# weather.net
KiCad netlist of a schematic drawn in EasyEDA Pro
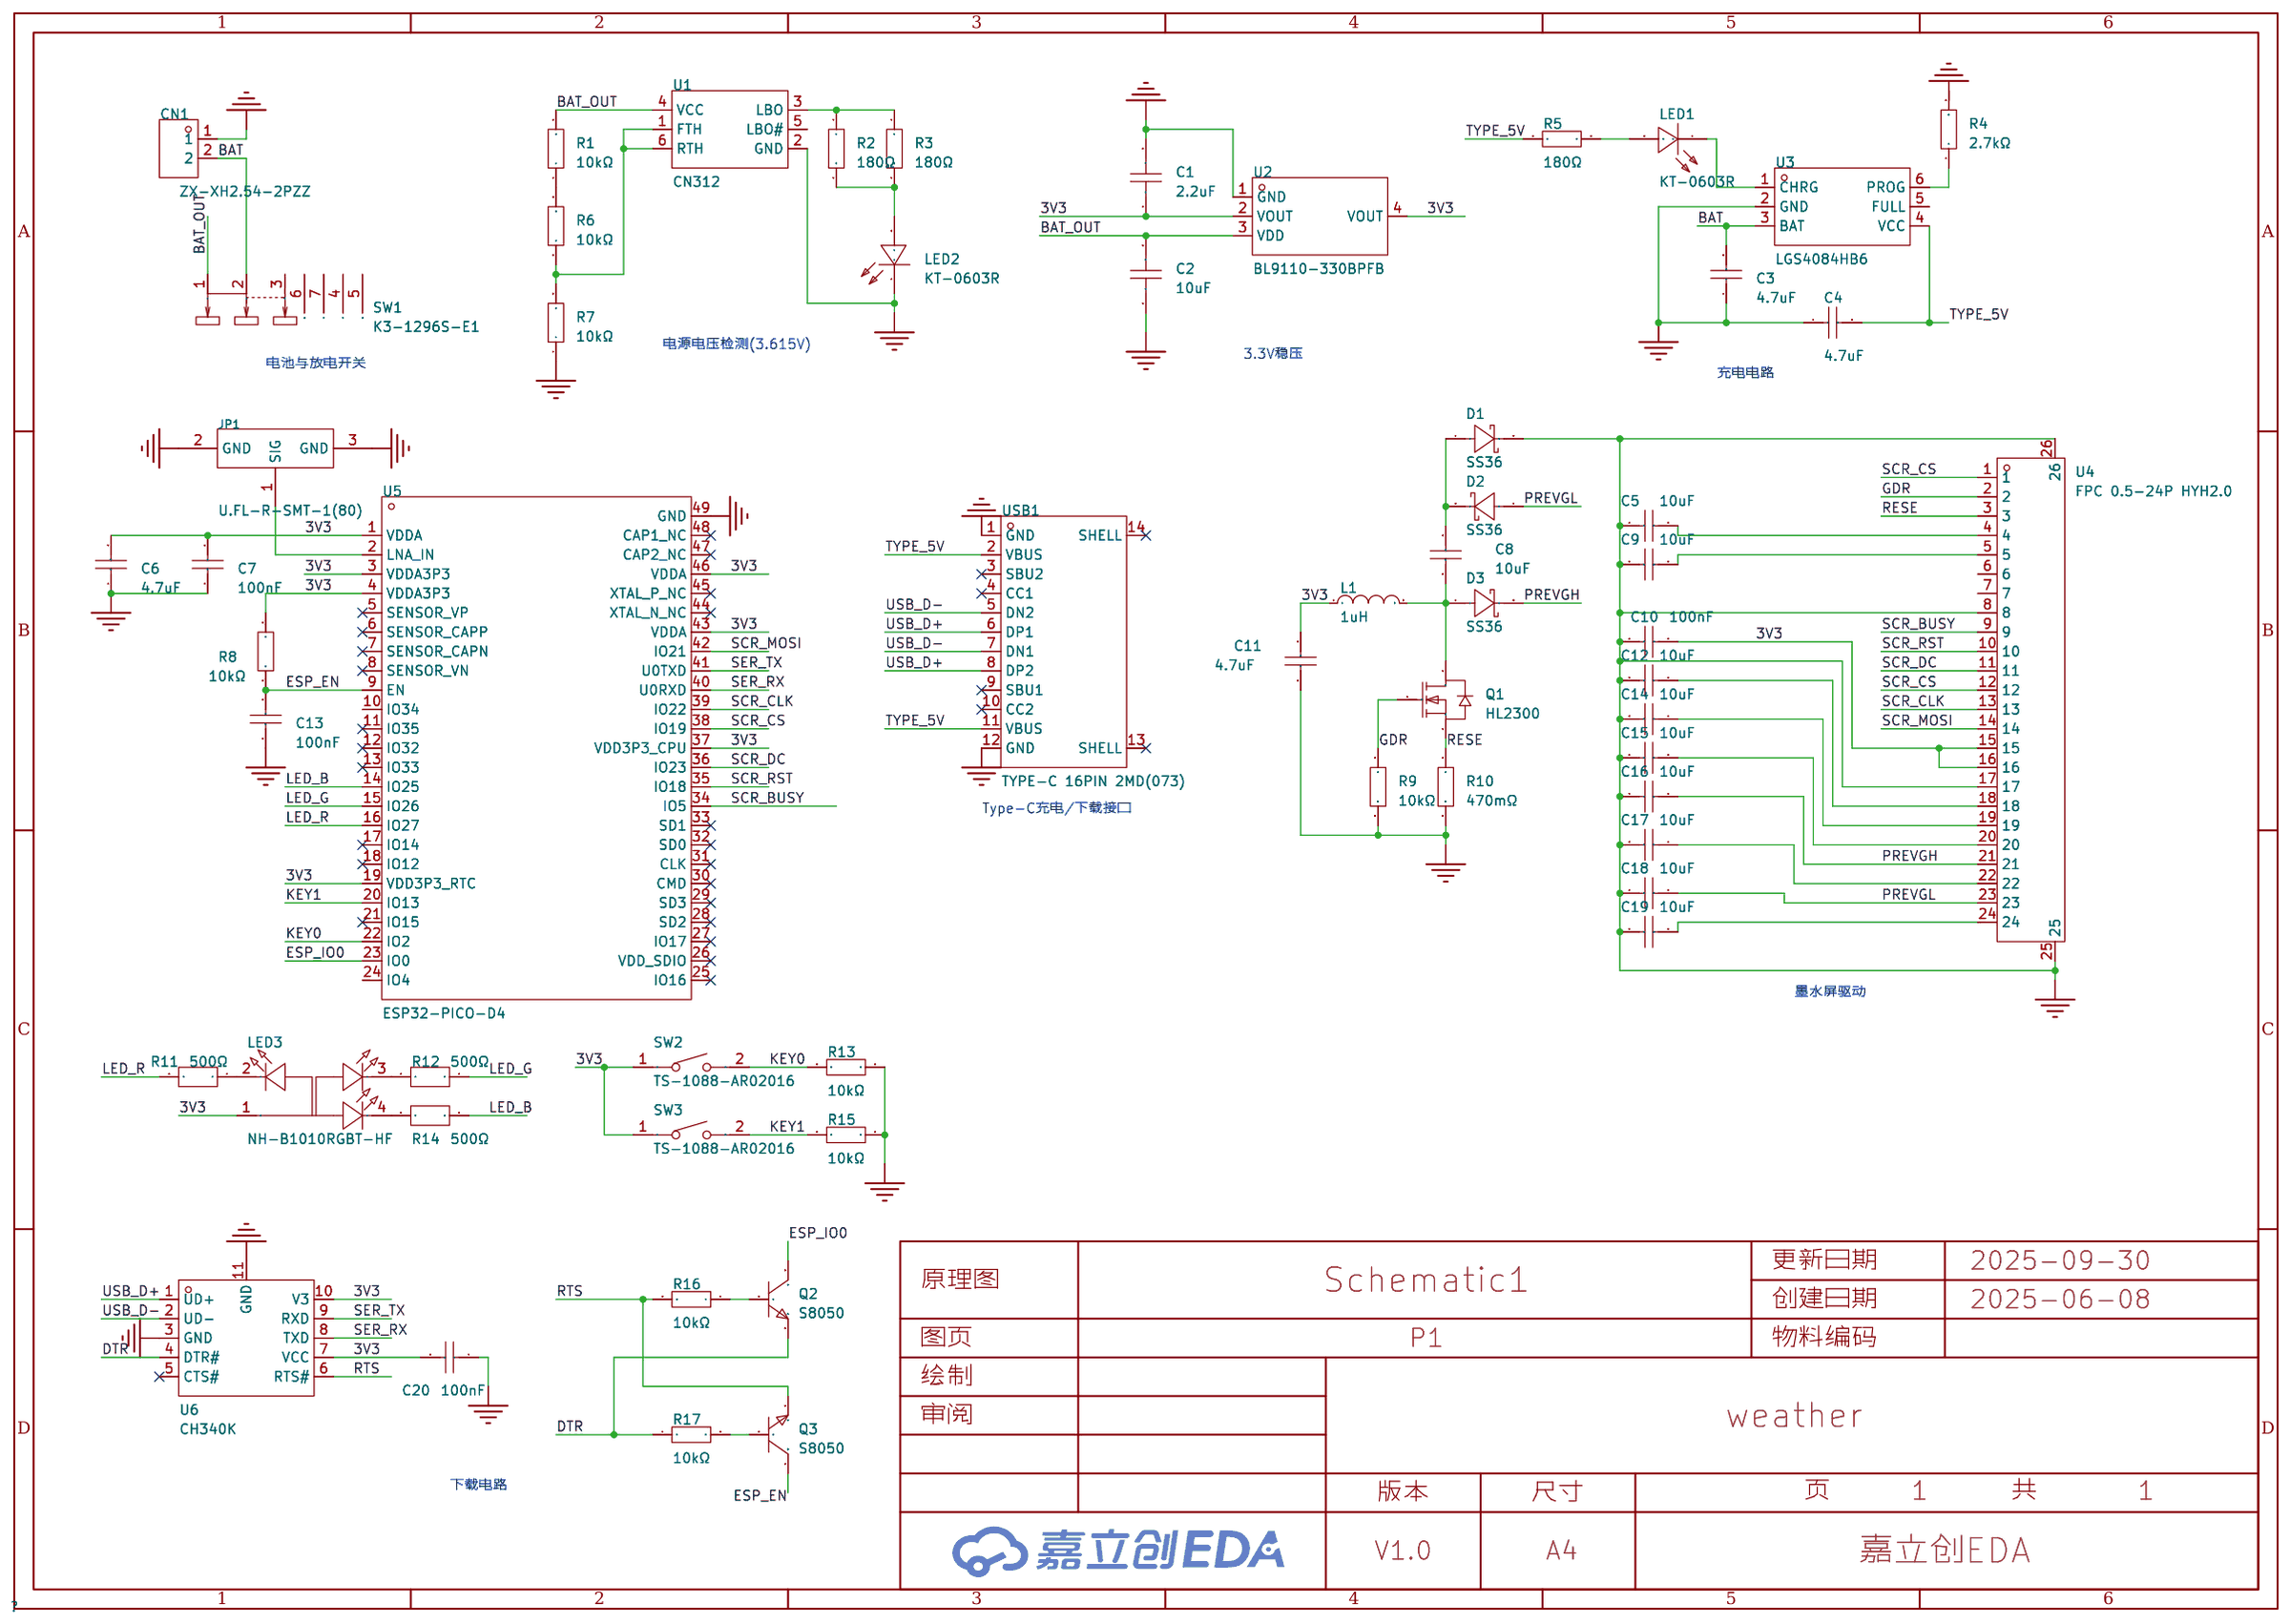
[diagram p0: schematic sheet]

(export (version "E")
  (design (tool "Eeschema 10.0.6"))
  (components
    (comp (ref "C1")
      (value "2.2uF")
      (footprint "easyedapro:C0402")
      (description "容值:2.2uF;精度:±10%;额定电压:16V;材质(温度系数):X5R;")
      (fields
        (field (name "Manufacturer Part") "HGC0402R5225K160NTEJ")
        (field (name "Manufacturer") "Chinocera(华瓷)")
      )
      (libsource (lib "easyedapro") (part "HGC0402R5225K160NTEJ"))
    )
    (comp (ref "C2")
      (value "10uF")
      (footprint "easyedapro:C0402")
      (description "容值:10uF;精度:±20%;额定电压:10V;材质(温度系数):X5R;")
      (fields
        (field (name "Manufacturer Part") "CGA0402X5R106M100GT")
        (field (name "Manufacturer") "HRE(芯声)")
      )
      (libsource (lib "easyedapro") (part "CGA0402X5R106M100GT"))
    )
    (comp (ref "C3")
      (value "4.7uF")
      (footprint "easyedapro:C0402")
      (description "容值:10uF;精度:±20%;额定电压:6.3V;材质(温度系数):X5R;")
      (fields
        (field (name "Manufacturer Part") "CL05A475MP5NRNC")
        (field (name "Manufacturer") "SAMSUNG(三星)")
      )
      (libsource (lib "easyedapro") (part "CL05A106MQ5NUNC"))
    )
    (comp (ref "C4")
      (value "4.7uF")
      (footprint "easyedapro:C0402")
      (description "容值:10uF;精度:±20%;额定电压:6.3V;材质(温度系数):X5R;")
      (fields
        (field (name "Manufacturer Part") "CL05A475MP5NRNC")
        (field (name "Manufacturer") "SAMSUNG(三星)")
      )
      (libsource (lib "easyedapro") (part "CL05A106MQ5NUNC"))
    )
    (comp (ref "C5")
      (value "10uF")
      (footprint "easyedapro:C0402")
      (description "容值:10uF;精度:±20%;额定电压:6.3V;材质(温度系数):X5R;")
      (fields
        (field (name "Manufacturer Part") "CL05A106MQ5NUNC")
        (field (name "Manufacturer") "SAMSUNG(三星)")
      )
      (libsource (lib "easyedapro") (part "CL05A106MQ5NUNC"))
    )
    (comp (ref "C6")
      (value "4.7uF")
      (footprint "easyedapro:C0402")
      (description "容值:10uF;精度:±20%;额定电压:6.3V;材质(温度系数):X5R;")
      (fields
        (field (name "Manufacturer Part") "CL05A475MP5NRNC")
        (field (name "Manufacturer") "SAMSUNG(三星)")
      )
      (libsource (lib "easyedapro") (part "CL05A106MQ5NUNC"))
    )
    (comp (ref "C7")
      (value "100nF")
      (footprint "easyedapro:C0402")
      (description "容值:100nF;精度:±10%;额定电压:16V;材质(温度系数):X7R;")
      (fields
        (field (name "Manufacturer Part") "CL05B104KO5NNNC")
        (field (name "Manufacturer") "SAMSUNG(三星)")
      )
      (libsource (lib "easyedapro") (part "CL05B104KO5NNNC"))
    )
    (comp (ref "C8")
      (value "10uF")
      (footprint "easyedapro:C0402")
      (description "容值:100nF;精度:±10%;额定电压:16V;温度系数:X7R;")
      (fields
        (field (name "Manufacturer Part") "CL05A106MQ5NUNC")
        (field (name "Manufacturer") "SAMSUNG(三星)")
      )
      (libsource (lib "easyedapro") (part "CL05A106MQ5NUNC"))
    )
    (comp (ref "C9")
      (value "10uF")
      (footprint "easyedapro:C0402")
      (description "容值:10uF;精度:±20%;额定电压:6.3V;材质(温度系数):X5R;")
      (fields
        (field (name "Manufacturer Part") "CL05A106MQ5NUNC")
        (field (name "Manufacturer") "SAMSUNG(三星)")
      )
      (libsource (lib "easyedapro") (part "CL05A106MQ5NUNC"))
    )
    (comp (ref "C10")
      (value "100nF")
      (footprint "easyedapro:C0402")
      (description "容值:100nF;精度:±10%;额定电压:16V;材质(温度系数):X7R;")
      (fields
        (field (name "Manufacturer Part") "CL05B104KO5NNNC")
        (field (name "Manufacturer") "SAMSUNG(三星)")
      )
      (libsource (lib "easyedapro") (part "CL05B104KO5NNNC"))
    )
    (comp (ref "C11")
      (value "4.7uF")
      (footprint "easyedapro:C0402")
      (description "容值:10uF;精度:±20%;额定电压:6.3V;材质(温度系数):X5R;")
      (fields
        (field (name "Manufacturer Part") "CL05A475MP5NRNC")
        (field (name "Manufacturer") "SAMSUNG(三星)")
      )
      (libsource (lib "easyedapro") (part "CL05A106MQ5NUNC"))
    )
    (comp (ref "C12")
      (value "10uF")
      (footprint "easyedapro:C0402")
      (description "容值:10uF;精度:±20%;额定电压:6.3V;材质(温度系数):X5R;")
      (fields
        (field (name "Manufacturer Part") "CL05A106MQ5NUNC")
        (field (name "Manufacturer") "SAMSUNG(三星)")
      )
      (libsource (lib "easyedapro") (part "CL05A106MQ5NUNC"))
    )
    (comp (ref "C13")
      (value "100nF")
      (footprint "easyedapro:C0402")
      (description "容值:100nF;精度:±10%;额定电压:16V;材质(温度系数):X7R;")
      (fields
        (field (name "Manufacturer Part") "CL05B104KO5NNNC")
        (field (name "Manufacturer") "SAMSUNG(三星)")
      )
      (libsource (lib "easyedapro") (part "CL05B104KO5NNNC"))
    )
    (comp (ref "C14")
      (value "10uF")
      (footprint "easyedapro:C0402")
      (description "容值:10uF;精度:±20%;额定电压:6.3V;材质(温度系数):X5R;")
      (fields
        (field (name "Manufacturer Part") "CL05A106MQ5NUNC")
        (field (name "Manufacturer") "SAMSUNG(三星)")
      )
      (libsource (lib "easyedapro") (part "CL05A106MQ5NUNC"))
    )
    (comp (ref "C15")
      (value "10uF")
      (footprint "easyedapro:C0402")
      (description "容值:10uF;精度:±20%;额定电压:6.3V;材质(温度系数):X5R;")
      (fields
        (field (name "Manufacturer Part") "CL05A106MQ5NUNC")
        (field (name "Manufacturer") "SAMSUNG(三星)")
      )
      (libsource (lib "easyedapro") (part "CL05A106MQ5NUNC"))
    )
    (comp (ref "C16")
      (value "10uF")
      (footprint "easyedapro:C0402")
      (description "容值:10uF;精度:±20%;额定电压:6.3V;材质(温度系数):X5R;")
      (fields
        (field (name "Manufacturer Part") "CL05A106MQ5NUNC")
        (field (name "Manufacturer") "SAMSUNG(三星)")
      )
      (libsource (lib "easyedapro") (part "CL05A106MQ5NUNC"))
    )
    (comp (ref "C17")
      (value "10uF")
      (footprint "easyedapro:C0402")
      (description "容值:10uF;精度:±20%;额定电压:6.3V;材质(温度系数):X5R;")
      (fields
        (field (name "Manufacturer Part") "CL05A106MQ5NUNC")
        (field (name "Manufacturer") "SAMSUNG(三星)")
      )
      (libsource (lib "easyedapro") (part "CL05A106MQ5NUNC"))
    )
    (comp (ref "C18")
      (value "10uF")
      (footprint "easyedapro:C0402")
      (description "容值:10uF;精度:±20%;额定电压:6.3V;材质(温度系数):X5R;")
      (fields
        (field (name "Manufacturer Part") "CL05A106MQ5NUNC")
        (field (name "Manufacturer") "SAMSUNG(三星)")
      )
      (libsource (lib "easyedapro") (part "CL05A106MQ5NUNC"))
    )
    (comp (ref "C19")
      (value "10uF")
      (footprint "easyedapro:C0402")
      (description "容值:10uF;精度:±20%;额定电压:6.3V;材质(温度系数):X5R;")
      (fields
        (field (name "Manufacturer Part") "CL05A106MQ5NUNC")
        (field (name "Manufacturer") "SAMSUNG(三星)")
      )
      (libsource (lib "easyedapro") (part "CL05A106MQ5NUNC"))
    )
    (comp (ref "C20")
      (value "100nF")
      (footprint "easyedapro:C0402")
      (description "容值:100nF;精度:±10%;额定电压:16V;材质(温度系数):X7R;")
      (fields
        (field (name "Manufacturer Part") "CL05B104KO5NNNC")
        (field (name "Manufacturer") "SAMSUNG(三星)")
      )
      (libsource (lib "easyedapro") (part "CL05B104KO5NNNC"))
    )
    (comp (ref "CN1")
      (value "ZX-XH2.54-2PZZ")
      (footprint "easyedapro:CONN-TH_2P-P2.50_HX25003-2A")
      (fields (field (name "Manufacturer") "Megastar(兆星)"))
      (libsource (lib "easyedapro") (part "ZX-XH2.54-2PZZ"))
    )
    (comp (ref "D1")
      (value "SS36")
      (footprint "easyedapro:SMA_L4.3-W2.6-LS5.0-FD")
      (description "二极管配置:独立式;正向压降(Vf):700mV@3.0A;直流反向耐压(Vr):60V;整流电流:3A;")
      (fields (field (name "Manufacturer") "R+O(宏嘉诚)"))
      (libsource (lib "easyedapro") (part "SS36_C7420367"))
    )
    (comp (ref "D2")
      (value "SS36")
      (footprint "easyedapro:SMA_L4.3-W2.6-LS5.0-FD")
      (description "二极管配置:独立式;正向压降(Vf):700mV@3.0A;直流反向耐压(Vr):60V;整流电流:3A;")
      (fields (field (name "Manufacturer") "R+O(宏嘉诚)"))
      (libsource (lib "easyedapro") (part "SS36_C7420367"))
    )
    (comp (ref "D3")
      (value "SS36")
      (footprint "easyedapro:SMA_L4.3-W2.6-LS5.0-FD")
      (description "二极管配置:独立式;正向压降(Vf):700mV@3.0A;直流反向耐压(Vr):60V;整流电流:3A;")
      (fields (field (name "Manufacturer") "R+O(宏嘉诚)"))
      (libsource (lib "easyedapro") (part "SS36_C7420367"))
    )
    (comp (ref "JP1")
      (value "U.FL-R-SMT-1(80)")
      (footprint "easyedapro:RF-SMD_FRF05002-JSS103M")
      (fields (field (name "Manufacturer") "HRS(广濑)"))
      (libsource (lib "easyedapro") (part "U.FL-R-SMT-1(80)"))
    )
    (comp (ref "L1")
      (value "1uH")
      (footprint "easyedapro:IND-SMD_L2.0-W1.6-B")
      (description "电感值:1uH;精度:±20%;额定电流:4.5A;饱和电流(Isat):4.6A;类型:一体成型电感;")
      (fields
        (field (name "Manufacturer Part") "FTC201610S1R0MBCA")
        (field (name "Manufacturer") "cjiang(长江微电)")
      )
      (libsource (lib "easyedapro") (part "FTC201610S1R0MBCA"))
    )
    (comp (ref "LED1")
      (value "KT-0603R")
      (footprint "easyedapro:LED0603-RD")
      (description "发光颜色:红色;功率:-;正向电流:-;主波长:-;二极管配置:-;透镜颜色:-;色温:-;发光角度:-;载带方式:-;工作温度:-40°C~+85°C;")
      (fields (field (name "Manufacturer") "KENTO"))
      (libsource (lib "easyedapro") (part "KT-0603R"))
    )
    (comp (ref "LED2")
      (value "KT-0603R")
      (footprint "easyedapro:LED0603-RD")
      (description "发光颜色:红色;功率:-;正向电流:-;主波长:-;二极管配置:-;透镜颜色:-;色温:-;发光角度:-;载带方式:-;工作温度:-40°C~+85°C;")
      (fields (field (name "Manufacturer") "KENTO"))
      (libsource (lib "easyedapro") (part "KT-0603R"))
    )
    (comp (ref "LED3")
      (value "NH-B1010RGBT-HF")
      (footprint "easyedapro:LED-ARRAY-SMD_4P-L1.0-W1.0-TR_NH-B1010RGBT")
      (description "户内RGB，全黑框架，对比度高，黑色哑光封装，无镜面反射")
      (fields (field (name "Manufacturer") "国星光电"))
      (libsource (lib "easyedapro") (part "NH-B1010RGBT-HF"))
    )
    (comp (ref "Q1")
      (value "HL2300")
      (footprint "easyedapro:SOT-23-3_L2.9-W1.3-P1.90-LS2.4-BR")
      (fields (field (name "Manufacturer") "R+O(宏嘉诚)"))
      (libsource (lib "easyedapro") (part "HL2300_C7420343"))
    )
    (comp (ref "Q2")
      (value "S8050")
      (footprint "easyedapro:SOT-23-3_L2.9-W1.6-P1.90-LS2.8-BR")
      (description "晶体管类型:NPN;集电极电流(Ic):500mA;集射极击穿电压(Vceo):25V;功率(Pd):300mW;")
      (fields (field (name "Manufacturer") "Hottech(合科泰)"))
      (libsource (lib "easyedapro") (part "S8050_C181158"))
    )
    (comp (ref "Q3")
      (value "S8050")
      (footprint "easyedapro:SOT-23-3_L2.9-W1.6-P1.90-LS2.8-BR")
      (description "晶体管类型:NPN;集电极电流(Ic):500mA;集射极击穿电压(Vceo):25V;功率(Pd):300mW;")
      (fields (field (name "Manufacturer") "Hottech(合科泰)"))
      (libsource (lib "easyedapro") (part "S8050_C181158"))
    )
    (comp (ref "R1")
      (value "10kΩ")
      (footprint "easyedapro:R0603")
      (description "电阻类型:厚膜电阻;阻值:10kΩ;精度:±1%;功率:100mW;最大工作电压:75V;温度系数:±100ppm/°C;")
      (fields
        (field (name "Manufacturer Part") "0402WGF1002TCE")
        (field (name "Manufacturer") "UNI-ROYAL(厚声)")
      )
      (libsource (lib "easyedapro") (part "0603WAF1002T5E"))
    )
    (comp (ref "R2")
      (value "180Ω")
      (fields
        (field (name "Manufacturer Part") "0402WGF1800TCE")
        (field (name "Manufacturer") "UNI-ROYAL(厚声)")
      )
      (libsource (lib "easyedapro") (part "0603WAF1800T5E"))
    )
    (comp (ref "R3")
      (value "180Ω")
      (fields
        (field (name "Manufacturer Part") "0402WGF1800TCE")
        (field (name "Manufacturer") "UNI-ROYAL(厚声)")
      )
      (libsource (lib "easyedapro") (part "0603WAF1800T5E"))
    )
    (comp (ref "R4")
      (value "2.7kΩ")
      (footprint "easyedapro:R0402")
      (description "电阻类型:厚膜电阻;阻值:2.7kΩ;精度:±1%;功率:62.5mW;最大工作电压:50V;温度系数:±100ppm/°C;")
      (fields
        (field (name "Manufacturer Part") "0402WGF2701TCE")
        (field (name "Manufacturer") "UNI-ROYAL(厚声)")
      )
      (libsource (lib "easyedapro") (part "0402WGF2701TCE"))
    )
    (comp (ref "R5")
      (value "180Ω")
      (fields
        (field (name "Manufacturer Part") "0402WGF1800TCE")
        (field (name "Manufacturer") "UNI-ROYAL(厚声)")
      )
      (libsource (lib "easyedapro") (part "0603WAF1800T5E"))
    )
    (comp (ref "R6")
      (value "10kΩ")
      (footprint "easyedapro:R0603")
      (description "电阻类型:厚膜电阻;阻值:10kΩ;精度:±1%;功率:100mW;最大工作电压:75V;温度系数:±100ppm/°C;")
      (fields
        (field (name "Manufacturer Part") "0402WGF1002TCE")
        (field (name "Manufacturer") "UNI-ROYAL(厚声)")
      )
      (libsource (lib "easyedapro") (part "0603WAF1002T5E"))
    )
    (comp (ref "R7")
      (value "10kΩ")
      (footprint "easyedapro:R0603")
      (description "电阻类型:厚膜电阻;阻值:10kΩ;精度:±1%;功率:100mW;最大工作电压:75V;温度系数:±100ppm/°C;")
      (fields
        (field (name "Manufacturer Part") "0402WGF1002TCE")
        (field (name "Manufacturer") "UNI-ROYAL(厚声)")
      )
      (libsource (lib "easyedapro") (part "0603WAF1002T5E"))
    )
    (comp (ref "R8")
      (value "10kΩ")
      (footprint "easyedapro:R0603")
      (description "电阻类型:厚膜电阻;阻值:10kΩ;精度:±1%;功率:100mW;最大工作电压:75V;温度系数:±100ppm/°C;")
      (fields
        (field (name "Manufacturer Part") "0402WGF1002TCE")
        (field (name "Manufacturer") "UNI-ROYAL(厚声)")
      )
      (libsource (lib "easyedapro") (part "0603WAF1002T5E"))
    )
    (comp (ref "R9")
      (value "10kΩ")
      (description "电阻类型:厚膜电阻;阻值:10kΩ;精度:±1%;功率:62.5mW;工作电压:50V;温度系数:±100ppm/℃;")
      (fields
        (field (name "Manufacturer Part") "0402WGF1002TCE")
        (field (name "Manufacturer") "UNI-ROYAL(厚声)")
      )
      (libsource (lib "easyedapro") (part "0603WAF1800T5E"))
    )
    (comp (ref "R10")
      (value "470mΩ")
      (fields
        (field (name "Manufacturer Part") "0402WGF470LTCE")
        (field (name "Manufacturer") "UNI-ROYAL(厚声)")
      )
      (libsource (lib "easyedapro") (part "0603WAF1800T5E"))
    )
    (comp (ref "R11")
      (value "500Ω")
      (footprint "easyedapro:R0402")
      (description "电阻类型:薄膜电阻;阻值:500Ω;精度:±1%;功率:63mW;温度系数:±50ppm/°C;")
      (fields (field (name "Manufacturer Part") "RT0402FRE07500RL") (field (name "Manufacturer") "YAGEO(国巨)"))
      (libsource (lib "easyedapro") (part "RT0402FRE07500RL"))
    )
    (comp (ref "R12")
      (value "500Ω")
      (footprint "easyedapro:R0402")
      (description "电阻类型:薄膜电阻;阻值:500Ω;精度:±1%;功率:63mW;温度系数:±50ppm/°C;")
      (fields (field (name "Manufacturer Part") "RT0402FRE07500RL") (field (name "Manufacturer") "YAGEO(国巨)"))
      (libsource (lib "easyedapro") (part "RT0402FRE07500RL"))
    )
    (comp (ref "R13")
      (value "10kΩ")
      (footprint "easyedapro:R0603")
      (description "电阻类型:厚膜电阻;阻值:10kΩ;精度:±1%;功率:100mW;最大工作电压:75V;温度系数:±100ppm/°C;")
      (fields
        (field (name "Manufacturer Part") "0402WGF1002TCE")
        (field (name "Manufacturer") "UNI-ROYAL(厚声)")
      )
      (libsource (lib "easyedapro") (part "0603WAF1002T5E"))
    )
    (comp (ref "R14")
      (value "500Ω")
      (footprint "easyedapro:R0402")
      (description "电阻类型:薄膜电阻;阻值:500Ω;精度:±1%;功率:63mW;温度系数:±50ppm/°C;")
      (fields (field (name "Manufacturer Part") "RT0402FRE07500RL") (field (name "Manufacturer") "YAGEO(国巨)"))
      (libsource (lib "easyedapro") (part "RT0402FRE07500RL"))
    )
    (comp (ref "R15")
      (value "10kΩ")
      (footprint "easyedapro:R0603")
      (description "电阻类型:厚膜电阻;阻值:10kΩ;精度:±1%;功率:100mW;最大工作电压:75V;温度系数:±100ppm/°C;")
      (fields
        (field (name "Manufacturer Part") "0402WGF1002TCE")
        (field (name "Manufacturer") "UNI-ROYAL(厚声)")
      )
      (libsource (lib "easyedapro") (part "0603WAF1002T5E"))
    )
    (comp (ref "R16")
      (value "10kΩ")
      (footprint "easyedapro:R0603")
      (description "电阻类型:厚膜电阻;阻值:10kΩ;精度:±1%;功率:100mW;最大工作电压:75V;温度系数:±100ppm/°C;")
      (fields
        (field (name "Manufacturer Part") "0402WGF1002TCE")
        (field (name "Manufacturer") "UNI-ROYAL(厚声)")
      )
      (libsource (lib "easyedapro") (part "0603WAF1002T5E"))
    )
    (comp (ref "R17")
      (value "10kΩ")
      (footprint "easyedapro:R0603")
      (description "电阻类型:厚膜电阻;阻值:10kΩ;精度:±1%;功率:100mW;最大工作电压:75V;温度系数:±100ppm/°C;")
      (fields
        (field (name "Manufacturer Part") "0402WGF1002TCE")
        (field (name "Manufacturer") "UNI-ROYAL(厚声)")
      )
      (libsource (lib "easyedapro") (part "0603WAF1002T5E"))
    )
    (comp (ref "SW1")
      (value "K3-1296S-E1")
      (footprint "easyedapro:SW-TH_K3-1296S-E1")
      (description "电路结构:单刀双掷;安装方式:卧贴;开关颜色:黑色;额定电流(DC):300mA;额定电压(DC):4V;额定电流(AC):-;额定电压(AC):-;机械寿命:1万次;")
      (fields (field (name "Manufacturer") "韩国韩荣"))
      (libsource (lib "easyedapro") (part "K3-1296S-E1_C128955"))
    )
    (comp (ref "SW2")
      (value "TS-1088-AR02016")
      (footprint "easyedapro:SW-SMD_L3.9-W3.0-P4.45")
      (fields (field (name "Manufacturer") "XUNPU(讯普)"))
      (libsource (lib "easyedapro") (part "TS-1088-AR02016"))
    )
    (comp (ref "SW3")
      (value "TS-1088-AR02016")
      (footprint "easyedapro:SW-SMD_L3.9-W3.0-P4.45")
      (fields (field (name "Manufacturer") "XUNPU(讯普)"))
      (libsource (lib "easyedapro") (part "TS-1088-AR02016"))
    )
    (comp (ref "U1")
      (value "CN312")
      (footprint "easyedapro:SOT-23-6_L2.9-W1.6-P0.95-LS2.8-BL")
      (description "集成电路")
      (fields (field (name "Manufacturer") "CONSONANCE(上海如韵)"))
      (libsource (lib "easyedapro") (part "CN312"))
    )
    (comp (ref "U2")
      (value "BL9110-330BPFB")
      (footprint "easyedapro:SOT-223_L6.5-W3.5-P2.30-LS7.0-BR")
      (description "输出类型:固定;最大输入电压:6V;输出电压:3.3V;最大输出电流:1A;电源纹波抑制比(PSRR):70dB@(1kHz);输出极性:正极;")
      (fields (field (name "Manufacturer") "BL(上海贝岭)"))
      (libsource (lib "easyedapro") (part "BL9110-330BPFB"))
    )
    (comp (ref "U3")
      (value "LGS4084HB6")
      (footprint "easyedapro:SOT-23-6_L2.9-W1.6-P0.95-LS2.8-BL")
      (description "电源电压:4V~6V;最大充电电流:500mA;电池类型:锂离子/聚合物;电池节数:1;")
      (fields (field (name "Manufacturer") "Legend-Si(棱晶半导体)"))
      (libsource (lib "easyedapro") (part "LGS4084HB6"))
    )
    (comp (ref "U4")
      (value "FPC 0.5-24P HYH2.0")
      (footprint "easyedapro:FPC-SMD_24P-P0.50_FPC-0.5-24P-HYH2.0")
      (description "锁定特性:翻盖式;触点类型:双侧触点/上下接;触点数量:24P;间距:0.5mm;安装方式:卧贴;工作温度:-25°C~+85°C;")
      (fields (field (name "Manufacturer") "SHOU HAN(首韩)"))
      (libsource (lib "easyedapro") (part "FPC 0.5-24P HYH2.0"))
    )
    (comp (ref "U5")
      (value "ESP32-PICO-D4")
      (footprint "easyedapro:LGA-48_L7.0-W7.0-P0.50-BL-EP5.4")
      (fields (field (name "Manufacturer") "ESPRESSIF(乐鑫)"))
      (libsource (lib "easyedapro") (part "ESP32-PICO-D4"))
    )
    (comp (ref "U6")
      (value "CH340K")
      (footprint "easyedapro:ESOP-10_L4.9-W3.9-P1.00-LS6.0-BL-EP")
      (fields (field (name "Manufacturer") "WCH(南京沁恒)"))
      (libsource (lib "easyedapro") (part "CH340K_C18208922"))
    )
    (comp (ref "USB1")
      (value "TYPE-C 16PIN 2MD(073)")
      (footprint "easyedapro:USB-C-SMD_TYPE-C-6PIN-2MD-073")
      (description "连接器类型:Type-C;标准:-;公母:母;端口数量:1;触点数量:16P;安装方式:卧贴;额定电流 - 电源:5A;工作温度范围:-25°C~+85°C;")
      (fields (field (name "Manufacturer") "SHOU HAN(首韩)"))
      (libsource (lib "easyedapro") (part "TYPE-C 16PIN 2MD(073)"))
    )
  )
  (nets
    (net (code "1") (name "/3V3") (class "Default")
      (node (ref "C1") (pin "1") (pinfunction "1_1") (pintype "unspecified"))
      (node (ref "C10") (pin "1") (pinfunction "1_1") (pintype "input"))
      (node (ref "C11") (pin "2") (pinfunction "2_2") (pintype "input"))
      (node (ref "C20") (pin "2") (pinfunction "2_2") (pintype "input"))
      (node (ref "C6") (pin "2") (pinfunction "2_2") (pintype "input"))
      (node (ref "C7") (pin "2") (pinfunction "2_2") (pintype "input"))
      (node (ref "L1") (pin "1") (pinfunction "1_1") (pintype "unspecified"))
      (node (ref "LED3") (pin "1") (pinfunction "+_1") (pintype "unspecified"))
      (node (ref "R8") (pin "1") (pinfunction "1_1") (pintype "input"))
      (node (ref "SW2") (pin "1") (pinfunction "1_1") (pintype "unspecified"))
      (node (ref "SW3") (pin "1") (pinfunction "1_1") (pintype "unspecified"))
      (node (ref "U2") (pin "2") (pinfunction "VOUT_2") (pintype "input"))
      (node (ref "U2") (pin "4") (pinfunction "VOUT_4") (pintype "input"))
      (node (ref "U4") (pin "15") (pinfunction "15_15") (pintype "unspecified"))
      (node (ref "U4") (pin "16") (pinfunction "16_16") (pintype "unspecified"))
      (node (ref "U5") (pin "1") (pinfunction "VDDA_1") (pintype "unspecified"))
      (node (ref "U5") (pin "19") (pinfunction "VDD3P3_RTC_19") (pintype "unspecified"))
      (node (ref "U5") (pin "3") (pinfunction "VDDA3P3_3") (pintype "unspecified"))
      (node (ref "U5") (pin "37") (pinfunction "VDD3P3_CPU_37") (pintype "unspecified"))
      (node (ref "U5") (pin "4") (pinfunction "VDDA3P3_4") (pintype "unspecified"))
      (node (ref "U5") (pin "43") (pinfunction "VDDA_43") (pintype "unspecified"))
      (node (ref "U5") (pin "46") (pinfunction "VDDA_46") (pintype "unspecified"))
      (node (ref "U6") (pin "10") (pinfunction "V3_10") (pintype "unspecified"))
      (node (ref "U6") (pin "7") (pinfunction "VCC_7") (pintype "unspecified"))
    )
    (net (code "2") (name "/BAT") (class "Default")
      (node (ref "C3") (pin "2") (pinfunction "2_2") (pintype "input"))
      (node (ref "CN1") (pin "2") (pinfunction "2_2") (pintype "unspecified"))
      (node (ref "SW1") (pin "2") (pinfunction "2_2") (pintype "unspecified"))
      (node (ref "U3") (pin "3") (pinfunction "BAT_3") (pintype "unspecified"))
    )
    (net (code "3") (name "/BAT_OUT") (class "Default")
      (node (ref "C2") (pin "2") (pinfunction "2_2") (pintype "unspecified"))
      (node (ref "R1") (pin "2") (pinfunction "2_2") (pintype "input"))
      (node (ref "SW1") (pin "1") (pinfunction "1_1") (pintype "unspecified"))
      (node (ref "U1") (pin "4") (pinfunction "VCC_4") (pintype "unspecified"))
      (node (ref "U2") (pin "3") (pinfunction "VDD_3") (pintype "input"))
    )
    (net (code "4") (name "/DTR") (class "Default")
      (node (ref "Q2") (pin "2") (pinfunction "2_2") (pintype "input"))
      (node (ref "R17") (pin "1") (pinfunction "1_1") (pintype "input"))
      (node (ref "U6") (pin "4") (pinfunction "DTR#_4") (pintype "unspecified"))
    )
    (net (code "5") (name "/ESP_EN") (class "Default")
      (node (ref "C13") (pin "2") (pinfunction "2_2") (pintype "input"))
      (node (ref "Q3") (pin "3") (pinfunction "3_3") (pintype "input"))
      (node (ref "R8") (pin "2") (pinfunction "2_2") (pintype "input"))
      (node (ref "U5") (pin "9") (pinfunction "EN_9") (pintype "unspecified"))
    )
    (net (code "6") (name "/ESP_IO0") (class "Default")
      (node (ref "Q2") (pin "3") (pinfunction "3_3") (pintype "input"))
      (node (ref "U5") (pin "23") (pinfunction "IO0_23") (pintype "unspecified"))
    )
    (net (code "7") (name "/GDR") (class "Default")
      (node (ref "Q1") (pin "1") (pinfunction "G_1") (pintype "unspecified"))
      (node (ref "R9") (pin "1") (pinfunction "1_1") (pintype "input"))
      (node (ref "U4") (pin "2") (pinfunction "2_2") (pintype "unspecified"))
    )
    (net (code "8") (name "/KEY0") (class "Default")
      (node (ref "R13") (pin "2") (pinfunction "2_2") (pintype "input"))
      (node (ref "SW2") (pin "2") (pinfunction "2_2") (pintype "unspecified"))
      (node (ref "U5") (pin "22") (pinfunction "IO2_22") (pintype "unspecified"))
    )
    (net (code "9") (name "/KEY1") (class "Default")
      (node (ref "R15") (pin "2") (pinfunction "2_2") (pintype "input"))
      (node (ref "SW3") (pin "2") (pinfunction "2_2") (pintype "unspecified"))
      (node (ref "U5") (pin "20") (pinfunction "IO13_20") (pintype "unspecified"))
    )
    (net (code "10") (name "/LED_B") (class "Default")
      (node (ref "R14") (pin "1") (pinfunction "1_1") (pintype "unspecified"))
      (node (ref "U5") (pin "14") (pinfunction "IO25_14") (pintype "unspecified"))
    )
    (net (code "11") (name "/LED_G") (class "Default")
      (node (ref "R12") (pin "1") (pinfunction "1_1") (pintype "unspecified"))
      (node (ref "U5") (pin "15") (pinfunction "IO26_15") (pintype "unspecified"))
    )
    (net (code "12") (name "/LED_R") (class "Default")
      (node (ref "R11") (pin "2") (pinfunction "2_2") (pintype "unspecified"))
      (node (ref "U5") (pin "16") (pinfunction "IO27_16") (pintype "unspecified"))
    )
    (net (code "13") (name "/PREVGH") (class "Default")
      (node (ref "C16") (pin "1") (pinfunction "1_1") (pintype "input"))
      (node (ref "D3") (pin "2") (pinfunction "K_2") (pintype "unspecified"))
      (node (ref "U4") (pin "21") (pinfunction "21_21") (pintype "unspecified"))
    )
    (net (code "14") (name "/PREVGL") (class "Default")
      (node (ref "C18") (pin "1") (pinfunction "1_1") (pintype "input"))
      (node (ref "D2") (pin "1") (pinfunction "A_1") (pintype "unspecified"))
      (node (ref "U4") (pin "23") (pinfunction "23_23") (pintype "unspecified"))
    )
    (net (code "15") (name "/RESE") (class "Default")
      (node (ref "Q1") (pin "2") (pinfunction "S_2") (pintype "unspecified"))
      (node (ref "R10") (pin "1") (pinfunction "1_1") (pintype "input"))
      (node (ref "U4") (pin "3") (pinfunction "3_3") (pintype "unspecified"))
    )
    (net (code "16") (name "/RTS") (class "Default")
      (node (ref "Q3") (pin "2") (pinfunction "2_2") (pintype "input"))
      (node (ref "R16") (pin "2") (pinfunction "2_2") (pintype "input"))
      (node (ref "U6") (pin "6") (pinfunction "RTS#_6") (pintype "unspecified"))
    )
    (net (code "17") (name "/SCR_BUSY") (class "Default")
      (node (ref "U4") (pin "9") (pinfunction "9_9") (pintype "unspecified"))
      (node (ref "U5") (pin "34") (pinfunction "IO5_34") (pintype "unspecified"))
    )
    (net (code "18") (name "/SCR_CLK") (class "Default")
      (node (ref "U4") (pin "13") (pinfunction "13_13") (pintype "unspecified"))
      (node (ref "U5") (pin "39") (pinfunction "IO22_39") (pintype "unspecified"))
    )
    (net (code "19") (name "/SCR_CS") (class "Default")
      (node (ref "U4") (pin "1") (pinfunction "1_1") (pintype "unspecified"))
      (node (ref "U4") (pin "12") (pinfunction "12_12") (pintype "unspecified"))
      (node (ref "U5") (pin "38") (pinfunction "IO19_38") (pintype "unspecified"))
    )
    (net (code "20") (name "/SCR_DC") (class "Default")
      (node (ref "U4") (pin "11") (pinfunction "11_11") (pintype "unspecified"))
      (node (ref "U5") (pin "36") (pinfunction "IO23_36") (pintype "unspecified"))
    )
    (net (code "21") (name "/SCR_MOSI") (class "Default")
      (node (ref "U4") (pin "14") (pinfunction "14_14") (pintype "unspecified"))
      (node (ref "U5") (pin "42") (pinfunction "IO21_42") (pintype "unspecified"))
    )
    (net (code "22") (name "/SCR_RST") (class "Default")
      (node (ref "U4") (pin "10") (pinfunction "10_10") (pintype "unspecified"))
      (node (ref "U5") (pin "35") (pinfunction "IO18_35") (pintype "unspecified"))
    )
    (net (code "23") (name "/SER_RX") (class "Default")
      (node (ref "U5") (pin "40") (pinfunction "U0RXD_40") (pintype "unspecified"))
      (node (ref "U6") (pin "8") (pinfunction "TXD_8") (pintype "unspecified"))
    )
    (net (code "24") (name "/SER_TX") (class "Default")
      (node (ref "U5") (pin "41") (pinfunction "U0TXD_41") (pintype "unspecified"))
      (node (ref "U6") (pin "9") (pinfunction "RXD_9") (pintype "unspecified"))
    )
    (net (code "25") (name "/TYPE_5V") (class "Default")
      (node (ref "C4") (pin "2") (pinfunction "2_2") (pintype "input"))
      (node (ref "R5") (pin "1") (pinfunction "1_1") (pintype "input"))
      (node (ref "U3") (pin "4") (pinfunction "VCC_4") (pintype "unspecified"))
      (node (ref "USB1") (pin "11") (pinfunction "VBUS_11") (pintype "unspecified"))
      (node (ref "USB1") (pin "2") (pinfunction "VBUS_2") (pintype "unspecified"))
    )
    (net (code "26") (name "/USB_D+") (class "Default")
      (node (ref "U6") (pin "1") (pinfunction "UD+_1") (pintype "unspecified"))
      (node (ref "USB1") (pin "6") (pinfunction "DP1_6") (pintype "unspecified"))
      (node (ref "USB1") (pin "8") (pinfunction "DP2_8") (pintype "unspecified"))
    )
    (net (code "27") (name "/USB_D-") (class "Default")
      (node (ref "U6") (pin "2") (pinfunction "UD-_2") (pintype "unspecified"))
      (node (ref "USB1") (pin "5") (pinfunction "DN2_5") (pintype "unspecified"))
      (node (ref "USB1") (pin "7") (pinfunction "DN1_7") (pintype "unspecified"))
    )
    (net (code "28") (name "GND") (class "Default")
      (node (ref "C1") (pin "2") (pinfunction "2_2") (pintype "unspecified"))
      (node (ref "C10") (pin "2") (pinfunction "2_2") (pintype "input"))
      (node (ref "C11") (pin "1") (pinfunction "1_1") (pintype "input"))
      (node (ref "C12") (pin "2") (pinfunction "2_2") (pintype "input"))
      (node (ref "C13") (pin "1") (pinfunction "1_1") (pintype "input"))
      (node (ref "C14") (pin "2") (pinfunction "2_2") (pintype "input"))
      (node (ref "C15") (pin "2") (pinfunction "2_2") (pintype "input"))
      (node (ref "C16") (pin "2") (pinfunction "2_2") (pintype "input"))
      (node (ref "C17") (pin "2") (pinfunction "2_2") (pintype "input"))
      (node (ref "C18") (pin "2") (pinfunction "2_2") (pintype "input"))
      (node (ref "C19") (pin "2") (pinfunction "2_2") (pintype "input"))
      (node (ref "C2") (pin "1") (pinfunction "1_1") (pintype "unspecified"))
      (node (ref "C20") (pin "1") (pinfunction "1_1") (pintype "input"))
      (node (ref "C3") (pin "1") (pinfunction "1_1") (pintype "input"))
      (node (ref "C4") (pin "1") (pinfunction "1_1") (pintype "input"))
      (node (ref "C5") (pin "2") (pinfunction "2_2") (pintype "input"))
      (node (ref "C6") (pin "1") (pinfunction "1_1") (pintype "input"))
      (node (ref "C7") (pin "1") (pinfunction "1_1") (pintype "input"))
      (node (ref "C9") (pin "2") (pinfunction "2_2") (pintype "input"))
      (node (ref "CN1") (pin "1") (pinfunction "1_1") (pintype "unspecified"))
      (node (ref "D1") (pin "2") (pinfunction "K_2") (pintype "unspecified"))
      (node (ref "JP1") (pin "2") (pinfunction "GND_2") (pintype "input"))
      (node (ref "JP1") (pin "3") (pinfunction "GND_3") (pintype "input"))
      (node (ref "LED2") (pin "1") (pinfunction "K_1") (pintype "input"))
      (node (ref "R10") (pin "2") (pinfunction "2_2") (pintype "input"))
      (node (ref "R13") (pin "1") (pinfunction "1_1") (pintype "input"))
      (node (ref "R15") (pin "1") (pinfunction "1_1") (pintype "input"))
      (node (ref "R4") (pin "2") (pinfunction "2_2") (pintype "input"))
      (node (ref "R7") (pin "1") (pinfunction "1_1") (pintype "input"))
      (node (ref "R9") (pin "2") (pinfunction "2_2") (pintype "input"))
      (node (ref "U1") (pin "2") (pinfunction "GND_2") (pintype "unspecified"))
      (node (ref "U2") (pin "1") (pinfunction "GND_1") (pintype "input"))
      (node (ref "U3") (pin "2") (pinfunction "GND_2") (pintype "unspecified"))
      (node (ref "U4") (pin "17") (pinfunction "17_17") (pintype "unspecified"))
      (node (ref "U4") (pin "25") (pinfunction "25_25") (pintype "unspecified"))
      (node (ref "U4") (pin "26") (pinfunction "26_26") (pintype "unspecified"))
      (node (ref "U4") (pin "8") (pinfunction "8_8") (pintype "unspecified"))
      (node (ref "U5") (pin "49") (pinfunction "GND_49") (pintype "unspecified"))
      (node (ref "U6") (pin "11") (pinfunction "GND_11") (pintype "unspecified"))
      (node (ref "U6") (pin "3") (pinfunction "GND_3") (pintype "unspecified"))
      (node (ref "USB1") (pin "1") (pinfunction "GND_1") (pintype "unspecified"))
      (node (ref "USB1") (pin "12") (pinfunction "GND_12") (pintype "unspecified"))
    )
    (net (code "29") (name "Net-(C5-Pad1)") (class "Default")
      (node (ref "C5") (pin "1") (pinfunction "1_1") (pintype "input"))
      (node (ref "U4") (pin "4") (pinfunction "4_4") (pintype "unspecified"))
    )
    (net (code "30") (name "Net-(C9-Pad1)") (class "Default")
      (node (ref "C9") (pin "1") (pinfunction "1_1") (pintype "input"))
      (node (ref "U4") (pin "5") (pinfunction "5_5") (pintype "unspecified"))
    )
    (net (code "31") (name "Net-(C12-Pad1)") (class "Default")
      (node (ref "C12") (pin "1") (pinfunction "1_1") (pintype "input"))
      (node (ref "U4") (pin "18") (pinfunction "18_18") (pintype "unspecified"))
    )
    (net (code "32") (name "Net-(C14-Pad1)") (class "Default")
      (node (ref "C14") (pin "1") (pinfunction "1_1") (pintype "input"))
      (node (ref "U4") (pin "19") (pinfunction "19_19") (pintype "unspecified"))
    )
    (net (code "33") (name "Net-(C15-Pad1)") (class "Default")
      (node (ref "C15") (pin "1") (pinfunction "1_1") (pintype "input"))
      (node (ref "U4") (pin "20") (pinfunction "20_20") (pintype "unspecified"))
    )
    (net (code "34") (name "Net-(C17-Pad1)") (class "Default")
      (node (ref "C17") (pin "1") (pinfunction "1_1") (pintype "input"))
      (node (ref "U4") (pin "22") (pinfunction "22_22") (pintype "unspecified"))
    )
    (net (code "35") (name "Net-(C19-Pad1)") (class "Default")
      (node (ref "C19") (pin "1") (pinfunction "1_1") (pintype "input"))
      (node (ref "U4") (pin "24") (pinfunction "24_24") (pintype "unspecified"))
    )
    (net (code "36") (name "Net-(D1-A)") (class "Default")
      (node (ref "C8") (pin "2") (pinfunction "2_2") (pintype "input"))
      (node (ref "D1") (pin "1") (pinfunction "A_1") (pintype "unspecified"))
      (node (ref "D2") (pin "2") (pinfunction "K_2") (pintype "unspecified"))
    )
    (net (code "37") (name "Net-(D3-A)") (class "Default")
      (node (ref "C8") (pin "1") (pinfunction "1_1") (pintype "input"))
      (node (ref "D3") (pin "1") (pinfunction "A_1") (pintype "unspecified"))
      (node (ref "L1") (pin "2") (pinfunction "2_2") (pintype "unspecified"))
      (node (ref "Q1") (pin "3") (pinfunction "D_3") (pintype "unspecified"))
    )
    (net (code "38") (name "Net-(JP1-SIG)") (class "Default")
      (node (ref "JP1") (pin "1") (pinfunction "SIG_1") (pintype "input"))
      (node (ref "U5") (pin "2") (pinfunction "LNA_IN_2") (pintype "unspecified"))
    )
    (net (code "39") (name "Net-(LED1-A)") (class "Default")
      (node (ref "LED1") (pin "2") (pinfunction "A_2") (pintype "input"))
      (node (ref "R5") (pin "2") (pinfunction "2_2") (pintype "input"))
    )
    (net (code "40") (name "Net-(LED1-K)") (class "Default")
      (node (ref "LED1") (pin "1") (pinfunction "K_1") (pintype "input"))
      (node (ref "U3") (pin "1") (pinfunction "CHRG_1") (pintype "unspecified"))
    )
    (net (code "41") (name "Net-(LED2-A)") (class "Default")
      (node (ref "LED2") (pin "2") (pinfunction "A_2") (pintype "input"))
      (node (ref "R2") (pin "2") (pinfunction "2_2") (pintype "input"))
      (node (ref "R3") (pin "2") (pinfunction "2_2") (pintype "input"))
    )
    (net (code "42") (name "Net-(LED3---Pad2)") (class "Default")
      (node (ref "LED3") (pin "2") (pinfunction "-_2") (pintype "unspecified"))
      (node (ref "R11") (pin "1") (pinfunction "1_1") (pintype "unspecified"))
    )
    (net (code "43") (name "Net-(LED3---Pad3)") (class "Default")
      (node (ref "LED3") (pin "3") (pinfunction "-_3") (pintype "unspecified"))
      (node (ref "R12") (pin "2") (pinfunction "2_2") (pintype "unspecified"))
    )
    (net (code "44") (name "Net-(LED3---Pad4)") (class "Default")
      (node (ref "LED3") (pin "4") (pinfunction "-_4") (pintype "unspecified"))
      (node (ref "R14") (pin "2") (pinfunction "2_2") (pintype "unspecified"))
    )
    (net (code "45") (name "Net-(Q2-Pad1)") (class "Default")
      (node (ref "Q2") (pin "1") (pinfunction "1_1") (pintype "input"))
      (node (ref "R16") (pin "1") (pinfunction "1_1") (pintype "input"))
    )
    (net (code "46") (name "Net-(Q3-Pad1)") (class "Default")
      (node (ref "Q3") (pin "1") (pinfunction "1_1") (pintype "input"))
      (node (ref "R17") (pin "2") (pinfunction "2_2") (pintype "input"))
    )
    (net (code "47") (name "Net-(R1-Pad1)") (class "Default")
      (node (ref "R1") (pin "1") (pinfunction "1_1") (pintype "input"))
      (node (ref "R6") (pin "2") (pinfunction "2_2") (pintype "input"))
    )
    (net (code "48") (name "Net-(U1-FTH)") (class "Default")
      (node (ref "R6") (pin "1") (pinfunction "1_1") (pintype "input"))
      (node (ref "R7") (pin "2") (pinfunction "2_2") (pintype "input"))
      (node (ref "U1") (pin "1") (pinfunction "FTH_1") (pintype "unspecified"))
      (node (ref "U1") (pin "6") (pinfunction "RTH_6") (pintype "unspecified"))
    )
    (net (code "49") (name "Net-(U1-LBO)") (class "Default")
      (node (ref "R2") (pin "1") (pinfunction "1_1") (pintype "input"))
      (node (ref "R3") (pin "1") (pinfunction "1_1") (pintype "input"))
      (node (ref "U1") (pin "3") (pinfunction "LBO_3") (pintype "unspecified"))
    )
    (net (code "50") (name "Net-(U3-PROG)") (class "Default")
      (node (ref "R4") (pin "1") (pinfunction "1_1") (pintype "input"))
      (node (ref "U3") (pin "6") (pinfunction "PROG_6") (pintype "unspecified"))
    )
    (net (code "51") (name "unconnected-(SW1-Pad3)") (class "Default")
      (node (ref "SW1") (pin "3") (pinfunction "3_3") (pintype "unspecified"))
    )
    (net (code "52") (name "unconnected-(SW1-Pad4)") (class "Default")
      (node (ref "SW1") (pin "4") (pinfunction "4_4") (pintype "unspecified"))
    )
    (net (code "53") (name "unconnected-(SW1-Pad5)") (class "Default")
      (node (ref "SW1") (pin "5") (pinfunction "5_5") (pintype "unspecified"))
    )
    (net (code "54") (name "unconnected-(SW1-Pad6)") (class "Default")
      (node (ref "SW1") (pin "6") (pinfunction "6_6") (pintype "unspecified"))
    )
    (net (code "55") (name "unconnected-(SW1-Pad7)") (class "Default")
      (node (ref "SW1") (pin "7") (pinfunction "7_7") (pintype "unspecified"))
    )
    (net (code "56") (name "unconnected-(U1-LBO#-Pad5)") (class "Default")
      (node (ref "U1") (pin "5") (pinfunction "LBO#_5") (pintype "unspecified"))
    )
    (net (code "57") (name "unconnected-(U3-FULL-Pad5)") (class "Default")
      (node (ref "U3") (pin "5") (pinfunction "FULL_5") (pintype "unspecified"))
    )
    (net (code "58") (name "unconnected-(U4-Pad6)") (class "Default")
      (node (ref "U4") (pin "6") (pinfunction "6_6") (pintype "unspecified"))
    )
    (net (code "59") (name "unconnected-(U4-Pad7)") (class "Default")
      (node (ref "U4") (pin "7") (pinfunction "7_7") (pintype "unspecified"))
    )
    (net (code "60") (name "unconnected-(U5-CAP1_NC-Pad48)") (class "Default")
      (node (ref "U5") (pin "48") (pinfunction "CAP1_NC_48") (pintype "unspecified+no_connect"))
    )
    (net (code "61") (name "unconnected-(U5-CAP2_NC-Pad47)") (class "Default")
      (node (ref "U5") (pin "47") (pinfunction "CAP2_NC_47") (pintype "unspecified+no_connect"))
    )
    (net (code "62") (name "unconnected-(U5-CLK-Pad31)") (class "Default")
      (node (ref "U5") (pin "31") (pinfunction "CLK_31") (pintype "unspecified+no_connect"))
    )
    (net (code "63") (name "unconnected-(U5-CMD-Pad30)") (class "Default")
      (node (ref "U5") (pin "30") (pinfunction "CMD_30") (pintype "unspecified+no_connect"))
    )
    (net (code "64") (name "unconnected-(U5-IO4-Pad24)") (class "Default")
      (node (ref "U5") (pin "24") (pinfunction "IO4_24") (pintype "unspecified"))
    )
    (net (code "65") (name "unconnected-(U5-IO12-Pad18)") (class "Default")
      (node (ref "U5") (pin "18") (pinfunction "IO12_18") (pintype "unspecified+no_connect"))
    )
    (net (code "66") (name "unconnected-(U5-IO14-Pad17)") (class "Default")
      (node (ref "U5") (pin "17") (pinfunction "IO14_17") (pintype "unspecified+no_connect"))
    )
    (net (code "67") (name "unconnected-(U5-IO15-Pad21)") (class "Default")
      (node (ref "U5") (pin "21") (pinfunction "IO15_21") (pintype "unspecified+no_connect"))
    )
    (net (code "68") (name "unconnected-(U5-IO16-Pad25)") (class "Default")
      (node (ref "U5") (pin "25") (pinfunction "IO16_25") (pintype "unspecified+no_connect"))
    )
    (net (code "69") (name "unconnected-(U5-IO17-Pad27)") (class "Default")
      (node (ref "U5") (pin "27") (pinfunction "IO17_27") (pintype "unspecified+no_connect"))
    )
    (net (code "70") (name "unconnected-(U5-IO32-Pad12)") (class "Default")
      (node (ref "U5") (pin "12") (pinfunction "IO32_12") (pintype "unspecified+no_connect"))
    )
    (net (code "71") (name "unconnected-(U5-IO33-Pad13)") (class "Default")
      (node (ref "U5") (pin "13") (pinfunction "IO33_13") (pintype "unspecified+no_connect"))
    )
    (net (code "72") (name "unconnected-(U5-IO34-Pad10)") (class "Default")
      (node (ref "U5") (pin "10") (pinfunction "IO34_10") (pintype "unspecified"))
    )
    (net (code "73") (name "unconnected-(U5-IO35-Pad11)") (class "Default")
      (node (ref "U5") (pin "11") (pinfunction "IO35_11") (pintype "unspecified+no_connect"))
    )
    (net (code "74") (name "unconnected-(U5-SD0-Pad32)") (class "Default")
      (node (ref "U5") (pin "32") (pinfunction "SD0_32") (pintype "unspecified+no_connect"))
    )
    (net (code "75") (name "unconnected-(U5-SD1-Pad33)") (class "Default")
      (node (ref "U5") (pin "33") (pinfunction "SD1_33") (pintype "unspecified+no_connect"))
    )
    (net (code "76") (name "unconnected-(U5-SD2-Pad28)") (class "Default")
      (node (ref "U5") (pin "28") (pinfunction "SD2_28") (pintype "unspecified+no_connect"))
    )
    (net (code "77") (name "unconnected-(U5-SD3-Pad29)") (class "Default")
      (node (ref "U5") (pin "29") (pinfunction "SD3_29") (pintype "unspecified+no_connect"))
    )
    (net (code "78") (name "unconnected-(U5-SENSOR_CAPN-Pad7)") (class "Default")
      (node (ref "U5") (pin "7") (pinfunction "SENSOR_CAPN_7") (pintype "unspecified+no_connect"))
    )
    (net (code "79") (name "unconnected-(U5-SENSOR_CAPP-Pad6)") (class "Default")
      (node (ref "U5") (pin "6") (pinfunction "SENSOR_CAPP_6") (pintype "unspecified+no_connect"))
    )
    (net (code "80") (name "unconnected-(U5-SENSOR_VN-Pad8)") (class "Default")
      (node (ref "U5") (pin "8") (pinfunction "SENSOR_VN_8") (pintype "unspecified+no_connect"))
    )
    (net (code "81") (name "unconnected-(U5-SENSOR_VP-Pad5)") (class "Default")
      (node (ref "U5") (pin "5") (pinfunction "SENSOR_VP_5") (pintype "unspecified+no_connect"))
    )
    (net (code "82") (name "unconnected-(U5-VDD_SDIO-Pad26)") (class "Default")
      (node (ref "U5") (pin "26") (pinfunction "VDD_SDIO_26") (pintype "unspecified+no_connect"))
    )
    (net (code "83") (name "unconnected-(U5-XTAL_N_NC-Pad44)") (class "Default")
      (node (ref "U5") (pin "44") (pinfunction "XTAL_N_NC_44") (pintype "unspecified+no_connect"))
    )
    (net (code "84") (name "unconnected-(U5-XTAL_P_NC-Pad45)") (class "Default")
      (node (ref "U5") (pin "45") (pinfunction "XTAL_P_NC_45") (pintype "unspecified+no_connect"))
    )
    (net (code "85") (name "unconnected-(U6-CTS#-Pad5)") (class "Default")
      (node (ref "U6") (pin "5") (pinfunction "CTS#_5") (pintype "unspecified+no_connect"))
    )
    (net (code "86") (name "unconnected-(USB1-CC1-Pad4)") (class "Default")
      (node (ref "USB1") (pin "4") (pinfunction "CC1_4") (pintype "unspecified+no_connect"))
    )
    (net (code "87") (name "unconnected-(USB1-CC2-Pad10)") (class "Default")
      (node (ref "USB1") (pin "10") (pinfunction "CC2_10") (pintype "unspecified+no_connect"))
    )
    (net (code "88") (name "unconnected-(USB1-SBU1-Pad9)") (class "Default")
      (node (ref "USB1") (pin "9") (pinfunction "SBU1_9") (pintype "unspecified+no_connect"))
    )
    (net (code "89") (name "unconnected-(USB1-SBU2-Pad3)") (class "Default")
      (node (ref "USB1") (pin "3") (pinfunction "SBU2_3") (pintype "unspecified+no_connect"))
    )
    (net (code "90") (name "unconnected-(USB1-SHELL-Pad13)") (class "Default")
      (node (ref "USB1") (pin "13") (pinfunction "SHELL_13") (pintype "unspecified+no_connect"))
    )
    (net (code "91") (name "unconnected-(USB1-SHELL-Pad14)") (class "Default")
      (node (ref "USB1") (pin "14") (pinfunction "SHELL_14") (pintype "unspecified+no_connect"))
    )
  )
)
